# PIC24E_Extension_Schematics.net
KiCad netlist of a schematic drawn in Altium Designer
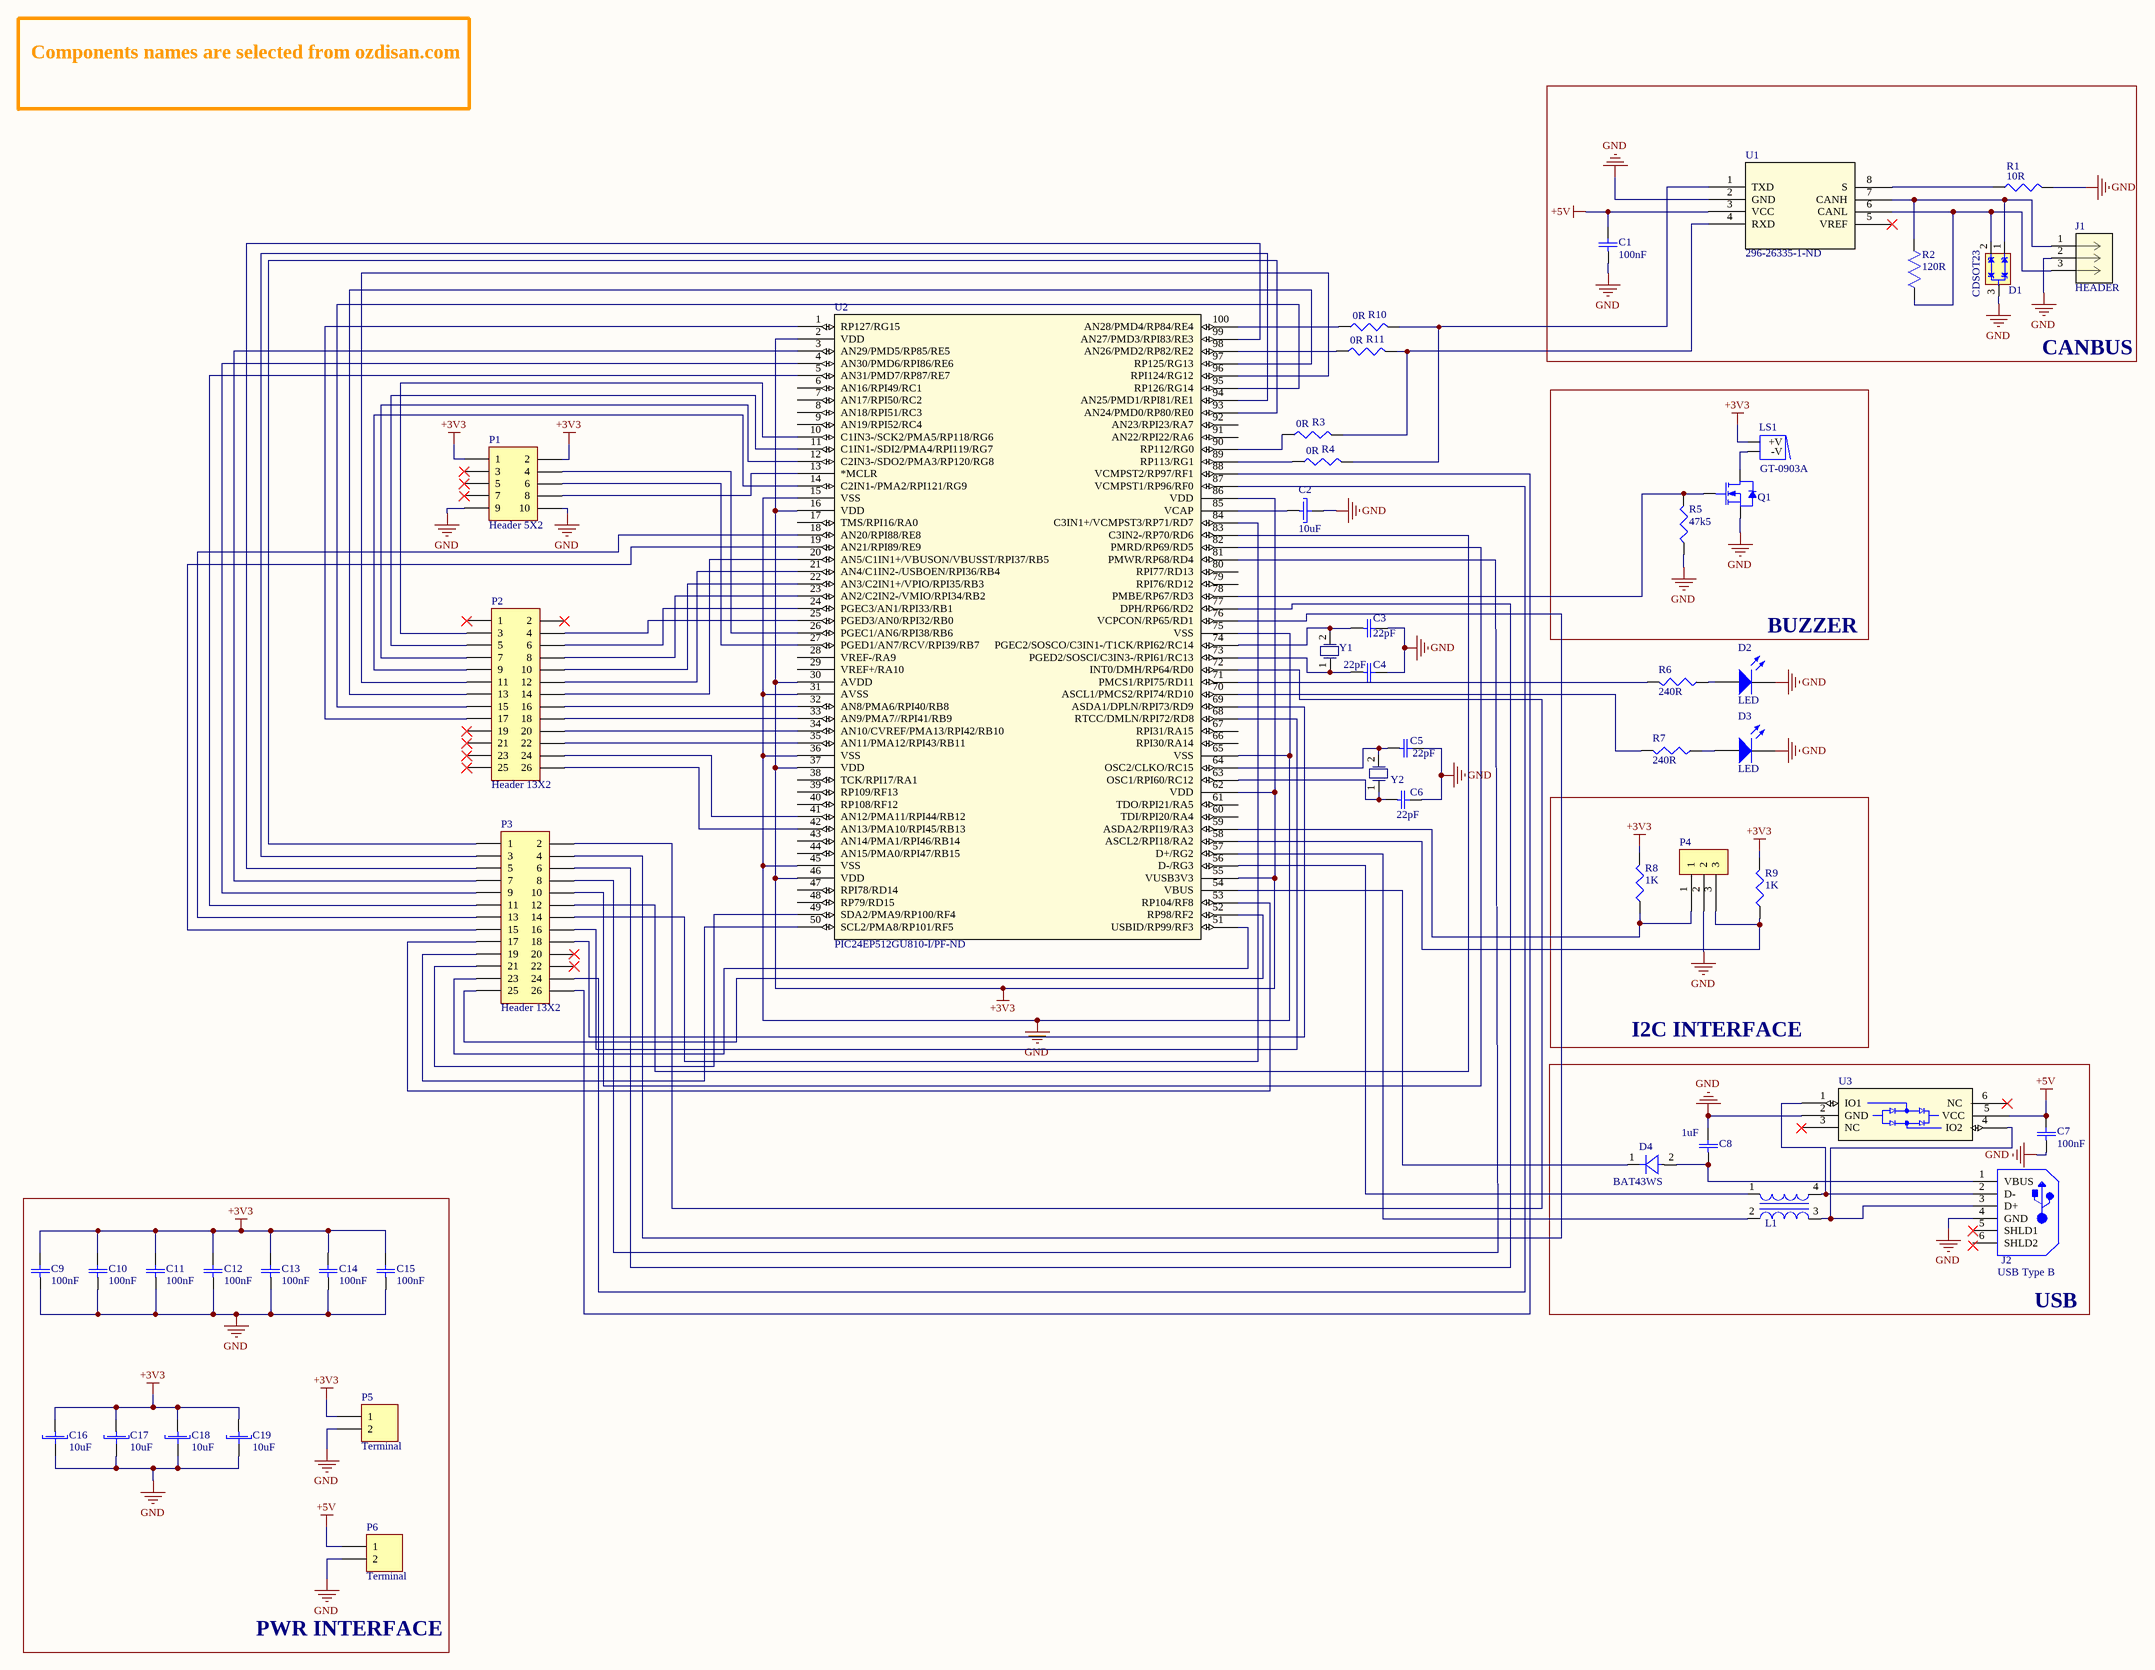
[diagram p0: PIC24E_Extension_Schematics.SchDoc]

(export (version "E")
  (design (tool "Eeschema 10.0.6"))
  (components
    (comp (ref "C1")
      (value "100nF")
      (footprint "SYNCBOX_V3I1:C1206")
      (description "MLCC (3216) 1206 100nF 100VDC ±10% X7R")
      (libsource (lib "SYNCBOX_TST") (part "CL05A104KA5NNNC"))
    )
    (comp (ref "C2")
      (value "10uF")
      (footprint "C1206 - TANT")
      (description "CAP.TANTAL 10uF 16V 10% A CASE (3216) SMD")
      (libsource (lib "SYNCBOX_TST") (part "T491A106K016AT"))
    )
    (comp (ref "C3")
      (value "22pF")
      (footprint "C1206")
      (description "MLCC (3216) 1206 22pF 50VDC ±5% C0G (NP0)")
      (libsource (lib "SYNCBOX_TST") (part "CL21A226MOCLRNC"))
    )
    (comp (ref "C4")
      (value "22pF")
      (footprint "C1206")
      (description "MLCC (3216) 1206 22pF 50VDC ±5% C0G (NP0)")
      (libsource (lib "SYNCBOX_TST") (part "CL21A226MOCLRNC"))
    )
    (comp (ref "C5")
      (value "22pF")
      (footprint "C1206")
      (description "MLCC (3216) 1206 22pF 50VDC ±5% C0G (NP0)")
      (libsource (lib "SYNCBOX_TST") (part "CL21A226MOCLRNC"))
    )
    (comp (ref "C6")
      (value "22pF")
      (footprint "C1206")
      (description "MLCC (3216) 1206 22pF 50VDC ±5% C0G (NP0)")
      (libsource (lib "SYNCBOX_TST") (part "CL21A226MOCLRNC"))
    )
    (comp (ref "C7")
      (value "100nF")
      (footprint "SYNCBOX_V3I1:C1206")
      (description "MLCC (3216) 1206 100nF 100VDC ±10% X7R")
      (libsource (lib "SYNCBOX_TST") (part "CL05A104KA5NNNC"))
    )
    (comp (ref "C8")
      (value "1uF")
      (footprint "SYNCBOX_TST:C1206")
      (description "MLCC (3216) 1206 1uF 16VDC ±5% X7R")
      (libsource (lib "SYNCBOX_V3I1") (part "CGA5L3X8R1H105K1"))
    )
    (comp (ref "C9")
      (value "100nF")
      (footprint "SYNCBOX_V3I1:C1206")
      (description "MLCC (3216) 1206 100nF 100VDC ±10% X7R")
      (libsource (lib "SYNCBOX_TST") (part "CL05A104KA5NNNC"))
    )
    (comp (ref "C10")
      (value "100nF")
      (footprint "SYNCBOX_V3I1:C1206")
      (description "MLCC (3216) 1206 100nF 100VDC ±10% X7R")
      (libsource (lib "SYNCBOX_TST") (part "CL05A104KA5NNNC"))
    )
    (comp (ref "C11")
      (value "100nF")
      (footprint "SYNCBOX_V3I1:C1206")
      (description "MLCC (3216) 1206 100nF 100VDC ±10% X7R")
      (libsource (lib "SYNCBOX_TST") (part "CL05A104KA5NNNC"))
    )
    (comp (ref "C12")
      (value "100nF")
      (footprint "SYNCBOX_V3I1:C1206")
      (description "MLCC (3216) 1206 100nF 100VDC ±10% X7R")
      (libsource (lib "SYNCBOX_TST") (part "CL05A104KA5NNNC"))
    )
    (comp (ref "C13")
      (value "100nF")
      (footprint "SYNCBOX_V3I1:C1206")
      (description "MLCC (3216) 1206 100nF 100VDC ±10% X7R")
      (libsource (lib "SYNCBOX_TST") (part "CL05A104KA5NNNC"))
    )
    (comp (ref "C14")
      (value "100nF")
      (footprint "SYNCBOX_V3I1:C1206")
      (description "MLCC (3216) 1206 100nF 100VDC ±10% X7R")
      (libsource (lib "SYNCBOX_TST") (part "CL05A104KA5NNNC"))
    )
    (comp (ref "C15")
      (value "100nF")
      (footprint "SYNCBOX_V3I1:C1206")
      (description "MLCC (3216) 1206 100nF 100VDC ±10% X7R")
      (libsource (lib "SYNCBOX_TST") (part "CL05A104KA5NNNC"))
    )
    (comp (ref "C16")
      (value "10uF")
      (footprint "C1206 - TANT")
      (description "CAP.TANTAL 10uF 16V 10% A CASE (3216) SMD")
      (libsource (lib "SYNCBOX_TST") (part "T491A106K016AT"))
    )
    (comp (ref "C17")
      (value "10uF")
      (footprint "C1206 - TANT")
      (description "CAP.TANTAL 10uF 16V 10% A CASE (3216) SMD")
      (libsource (lib "SYNCBOX_TST") (part "T491A106K016AT"))
    )
    (comp (ref "C18")
      (value "10uF")
      (footprint "C1206 - TANT")
      (description "CAP.TANTAL 10uF 16V 10% A CASE (3216) SMD")
      (libsource (lib "SYNCBOX_TST") (part "T491A106K016AT"))
    )
    (comp (ref "C19")
      (value "10uF")
      (footprint "C1206 - TANT")
      (description "CAP.TANTAL 10uF 16V 10% A CASE (3216) SMD")
      (libsource (lib "SYNCBOX_TST") (part "T491A106K016AT"))
    )
    (comp (ref "D1")
      (value "CDSOT23")
      (footprint "SOT-23-3")
      (description "DIODE TVS 24VWM 40VC SOT23")
      (libsource (lib "SYNCBOX_V3I1") (part "CDSOT23"))
    )
    (comp (ref "D2")
      (value "LED")
      (footprint "D0603_Directional")
      (description "LED RED DIFFUSED 0603 SMD")
      (fields (field (name "PUBLISHER") "Altium Limited"))
      (libsource (lib "SYNCBOX_V3I1") (part "LS Q976-NR-1"))
    )
    (comp (ref "D3")
      (value "LED")
      (footprint "D0603_Directional")
      (description "LED RED DIFFUSED 0603 SMD")
      (fields (field (name "PUBLISHER") "Altium Limited"))
      (libsource (lib "SYNCBOX_V3I1") (part "LS Q976-NR-1"))
    )
    (comp (ref "D4")
      (value "BAT43WS")
      (footprint "SOD323")
      (description "DIODE SCHOTTKY 30V 200MA SOD323")
      (libsource (lib "SYNCBOX_V3I1") (part "BAT43WS-7-F"))
    )
    (comp (ref "J1")
      (value "HEADER")
      (footprint "TerminalBlock3P508")
      (description "PIN HEADER 3PIN(1x3) 2.00mm THT V/T")
      (libsource (lib "SYNCBOX_V3I1") (part "796644-3"))
    )
    (comp (ref "J2")
      (value "USB Type B")
      (footprint "USB-B RECEPTACLE")
      (description "CONNECTOR USB B TYPE RIGHT ANGLE 90C CONNFLY")
      (libsource (lib "TE Audio, Video and High Speed Serial Connectors") (part "292304-1"))
    )
    (comp (ref "L1")
      (value "ACM2012-900-2P-T002")
      (footprint "ACM2012")
      (description "CHOKE COMM MODE 90 OHM .4A SMD")
      (fields
        (field (name "MANUFACTURER") "TDK Corporation")
        (field (name "TOLERANCE") "±1%")
        (field (name ".CHECKED PCB") "CHK")
        (field (name ".CHECKED SCH") "CHK")
      )
      (libsource (lib "SYNCBOX_V3I1") (part "ACM2012-900-2P-T002"))
    )
    (comp (ref "LS1")
      (value "GT-0903A")
      (footprint "GT-0903A")
      (description "AUDIO MAGNETIC XDCR 2-4V TH")
      (libsource (lib "SYNCBOX_V3I1") (part "GT-0903A"))
    )
    (comp (ref "P1")
      (value "Header 5X2")
      (footprint "HDR2X5")
      (description "CONNECTOR 2.54MM 10P (5X2) MALE")
      (libsource (lib "Miscellaneous Connectors") (part "Header 5X2"))
    )
    (comp (ref "P2")
      (value "Header 13X2")
      (footprint "HDR2X13")
      (description "PIN HEADER 26PIN(2x13) 2.54mm THT V/T MALE 180 C")
      (libsource (lib "Miscellaneous Connectors") (part "Header 13X2"))
    )
    (comp (ref "P3")
      (value "Header 13X2")
      (footprint "HDR2X13")
      (description "PIN HEADER 26PIN(2x13) 2.54mm THT V/T MALE 180 C")
      (libsource (lib "Miscellaneous Connectors") (part "Header 13X2"))
    )
    (comp (ref "P4")
      (value "76384-303LF")
      (footprint "HDR_1x3_2.54MM_SHDR_V2")
      (description "CONN HEADER 3POS .100\" STR GOLD")
      (fields
        (field (name "MANUFACTURER") "FCI")
        (field (name ".CREATOR") "MM")
        (field (name ".CHECKED PCB") "CHK")
        (field (name ".CHECKED SCH") "CHK")
      )
      (libsource (lib "SYNCBOX_V3I1") (part "76384-303LF"))
    )
    (comp (ref "P5")
      (value "Terminal")
      (footprint "SYNCBOX_TST:SRW_TRM")
      (description "TERM.BLK.3.50MM 2P PCB TYPE GREEN")
      (libsource (lib "Miscellaneous Connectors") (part "Header 2"))
    )
    (comp (ref "P6")
      (value "Terminal")
      (footprint "SYNCBOX_TST:SRW_TRM")
      (description "TERM.BLK.5.00MM 3P PCB TYPE 0 BOY GREEN GOLTEN")
      (libsource (lib "Miscellaneous Connectors") (part "Header 2"))
    )
    (comp (ref "Q1")
      (value "MOSFET N-CH 20V 1A SOT323")
      (footprint "SC70_SOT323")
      (fields (field (name "PUBLISHER") "Altium Limited"))
      (libsource (lib "SYNCBOX_V3I1") (part "DMG1012UW-7"))
    )
    (comp (ref "R1")
      (value "10R")
      (footprint "R1206")
      (description "RES.(3216) 1206 10 Ohms 1% 1/4W-S 400PPM")
      (libsource (lib "SYNCBOX_V3I1") (part "RC0402FR-0710RL"))
    )
    (comp (ref "R2")
      (value "120R")
      (footprint "R1206")
      (description "RES.(3216) 1206 120 Ohms 1% 1/4W-S 100PPM")
      (libsource (lib "SYNCBOX_V3I1") (part "RL1632R-R120-F"))
    )
    (comp (ref "R3")
      (value "0R")
      (footprint "R1206")
      (description "RES.(3216) 1206 0 Ohms 5% 1/4W-S 800PPM")
      (libsource (lib "SYNCBOX_V3I1") (part "RC0402FR-0710RL"))
    )
    (comp (ref "R4")
      (value "0R")
      (footprint "R1206")
      (description "RES.(3216) 1206 0 Ohms 5% 1/4W-S 800PPM")
      (libsource (lib "SYNCBOX_V3I1") (part "RC0402FR-0710RL"))
    )
    (comp (ref "R5")
      (value "47k5")
      (footprint "R1206")
      (description "RES.(3216) 1206 47.5K Ohms 1% 1/4W-S 100PPM")
      (libsource (lib "SYNCBOX_V3I1") (part "RC0402FR-0747K5L"))
    )
    (comp (ref "R6")
      (value "240R")
      (footprint "R1206")
      (description "RES.(3216) 1206 240 Ohms 1% 1/4W-S 100PPM")
      (libsource (lib "SYNCBOX_V3I1") (part "RMCF0402FT240R"))
    )
    (comp (ref "R7")
      (value "240R")
      (footprint "R1206")
      (description "RES.(3216) 1206 240 Ohms 1% 1/4W-S 100PPM")
      (libsource (lib "SYNCBOX_V3I1") (part "RMCF0402FT240R"))
    )
    (comp (ref "R8")
      (value "1K")
      (footprint "R1206")
      (description "RES.(3216) 1206 1K Ohms 1% 1/4W-S 100PPM")
      (libsource (lib "SYNCBOX_V3I1") (part "ERJ-2RKF1001X"))
    )
    (comp (ref "R9")
      (value "1K")
      (footprint "R1206")
      (description "RES.(3216) 1206 1K Ohms 1% 1/4W-S 100PPM")
      (libsource (lib "SYNCBOX_V3I1") (part "ERJ-2RKF1001X"))
    )
    (comp (ref "R10")
      (value "0R")
      (footprint "R1206")
      (description "RES.(3216) 1206 0 Ohms 5% 1/4W-S 800PPM")
      (libsource (lib "SYNCBOX_V3I1") (part "RC0402FR-0710RL"))
    )
    (comp (ref "R11")
      (value "0R")
      (footprint "R1206")
      (description "RES.(3216) 1206 0 Ohms 5% 1/4W-S 800PPM")
      (libsource (lib "SYNCBOX_V3I1") (part "RC0402FR-0710RL"))
    )
    (comp (ref "U1")
      (value "296-26335-1-ND")
      (footprint "D8")
      (description "IC EMC CAN TRANSCEIVER 8-SOIC")
      (fields
        (field (name "MANUFACTURER") "Texas Instruments")
        (field (name "MANUFACTURER_PART_NUMBER") "SN65HVD1050DR")
        (field (name ".CHECKED PCB") "CHK")
        (field (name ".CHECKED SCH") "CHK")
      )
      (libsource (lib "SYNCBOX_V3I1") (part "SN65HVD1050DR"))
    )
    (comp (ref "U2")
      (value "PIC24EP512GU810-I/PF-ND")
      (footprint "TQFP100_14x14MC")
      (description "IC MCU 16BIT 512KB FLASH 100TQFP")
      (fields
        (field (name "MANUFACTURER_PART_NUMBER") "PIC24EP512GU810-I/PT")
        (field (name "BASE PART NUMBER") "PIC24EP512GU810")
        (field (name ".CHECKED PCB") "CHK")
        (field (name ".CHECKED SCH") "CHK")
      )
      (libsource (lib "SYNCBOX_TST") (part "PIC24EP512GU810-"))
    )
    (comp (ref "U3")
      (value "TVS DIODE 5V 8.1V SOT23-6")
      (footprint "21-0058I")
      (description "MAX3207E")
      (fields
        (field (name "MANUFACTURER_PART_NUMBER") "MAX3207EAUT+T")
        (field (name ".CHECKED PCB") "CHK")
        (field (name ".CHECKED SCH") "CHK")
      )
      (libsource (lib "SYNCBOX_V3I1") (part "MAX3207EAUT+T"))
    )
    (comp (ref "Y1")
      (value "XTAL-32.7680kHz")
      (footprint "SYNCBOX_TST:C0805 - OSC")
      (description "CRYSTAL 32.7680kHz 20ppm 12.5pF SMD")
      (libsource (lib "SYNCBOX_TST") (part "Crystal-8MHz"))
    )
    (comp (ref "Y2")
      (value "XTAL-8MHz")
      (footprint "SYNCBOX_TST:HC49/US")
      (description "CRYSTAL 8.0000MHZ 18PF SMD")
      (libsource (lib "SYNCBOX_TST") (part "Crystal-8MHz"))
    )
  )
  (nets
    (net (code "1") (name "+3V3") (class "Default")
      (node (ref "C10") (pin "2") (pinfunction "2_2") (pintype "passive"))
      (node (ref "C11") (pin "2") (pinfunction "2_2") (pintype "passive"))
      (node (ref "C12") (pin "2") (pinfunction "2_2") (pintype "passive"))
      (node (ref "C13") (pin "2") (pinfunction "2_2") (pintype "passive"))
      (node (ref "C14") (pin "2") (pinfunction "2_2") (pintype "passive"))
      (node (ref "C15") (pin "2") (pinfunction "2_2") (pintype "passive"))
      (node (ref "C16") (pin "1") (pinfunction "1_1") (pintype "passive"))
      (node (ref "C17") (pin "1") (pinfunction "1_1") (pintype "passive"))
      (node (ref "C18") (pin "1") (pinfunction "1_1") (pintype "passive"))
      (node (ref "C19") (pin "1") (pinfunction "1_1") (pintype "passive"))
      (node (ref "C9") (pin "2") (pinfunction "2_2") (pintype "passive"))
      (node (ref "LS1") (pin "1") (pinfunction "+V_1") (pintype "passive"))
      (node (ref "P1") (pin "1") (pinfunction "1_1") (pintype "passive"))
      (node (ref "P1") (pin "2") (pinfunction "2_2") (pintype "passive"))
      (node (ref "P5") (pin "1") (pinfunction "1_1") (pintype "passive"))
      (node (ref "R8") (pin "2") (pinfunction "2_2") (pintype "passive"))
      (node (ref "R9") (pin "2") (pinfunction "2_2") (pintype "passive"))
      (node (ref "U2") (pin "16") (pinfunction "VDD_16") (pintype "passive"))
      (node (ref "U2") (pin "2") (pinfunction "VDD_2") (pintype "passive"))
      (node (ref "U2") (pin "30") (pinfunction "AVDD_30") (pintype "passive"))
      (node (ref "U2") (pin "37") (pinfunction "VDD_37") (pintype "passive"))
      (node (ref "U2") (pin "46") (pinfunction "VDD_46") (pintype "passive"))
      (node (ref "U2") (pin "55") (pinfunction "VUSB3V3_55") (pintype "passive"))
      (node (ref "U2") (pin "62") (pinfunction "VDD_62") (pintype "passive"))
      (node (ref "U2") (pin "86") (pinfunction "VDD_86") (pintype "passive"))
    )
    (net (code "2") (name "+5V") (class "Default")
      (node (ref "C1") (pin "2") (pinfunction "2_2") (pintype "passive"))
      (node (ref "C7") (pin "2") (pinfunction "2_2") (pintype "passive"))
      (node (ref "P6") (pin "1") (pinfunction "1_1") (pintype "passive"))
      (node (ref "U1") (pin "3") (pinfunction "VCC_3") (pintype "power_in"))
      (node (ref "U3") (pin "5") (pinfunction "VCC_5") (pintype "power_in"))
    )
    (net (code "3") (name "GND") (class "Default")
      (node (ref "C1") (pin "1") (pinfunction "1_1") (pintype "passive"))
      (node (ref "C10") (pin "1") (pinfunction "1_1") (pintype "passive"))
      (node (ref "C11") (pin "1") (pinfunction "1_1") (pintype "passive"))
      (node (ref "C12") (pin "1") (pinfunction "1_1") (pintype "passive"))
      (node (ref "C13") (pin "1") (pinfunction "1_1") (pintype "passive"))
      (node (ref "C14") (pin "1") (pinfunction "1_1") (pintype "passive"))
      (node (ref "C15") (pin "1") (pinfunction "1_1") (pintype "passive"))
      (node (ref "C16") (pin "2") (pinfunction "2_2") (pintype "passive"))
      (node (ref "C17") (pin "2") (pinfunction "2_2") (pintype "passive"))
      (node (ref "C18") (pin "2") (pinfunction "2_2") (pintype "passive"))
      (node (ref "C19") (pin "2") (pinfunction "2_2") (pintype "passive"))
      (node (ref "C2") (pin "2") (pinfunction "2_2") (pintype "passive"))
      (node (ref "C3") (pin "2") (pinfunction "2_2") (pintype "passive"))
      (node (ref "C4") (pin "2") (pinfunction "2_2") (pintype "passive"))
      (node (ref "C5") (pin "2") (pinfunction "2_2") (pintype "passive"))
      (node (ref "C6") (pin "2") (pinfunction "2_2") (pintype "passive"))
      (node (ref "C7") (pin "1") (pinfunction "1_1") (pintype "passive"))
      (node (ref "C8") (pin "2") (pinfunction "2_2") (pintype "passive"))
      (node (ref "C9") (pin "1") (pinfunction "1_1") (pintype "passive"))
      (node (ref "D1") (pin "3") (pinfunction "3_3") (pintype "passive"))
      (node (ref "D2") (pin "2") (pinfunction "K_2") (pintype "passive"))
      (node (ref "D3") (pin "2") (pinfunction "K_2") (pintype "passive"))
      (node (ref "J1") (pin "2") (pinfunction "2_2") (pintype "passive"))
      (node (ref "J2") (pin "4") (pinfunction "GND_4") (pintype "passive"))
      (node (ref "P1") (pin "10") (pinfunction "10_10") (pintype "passive"))
      (node (ref "P1") (pin "9") (pinfunction "9_9") (pintype "passive"))
      (node (ref "P4") (pin "2") (pinfunction "2_2") (pintype "passive"))
      (node (ref "P5") (pin "2") (pinfunction "2_2") (pintype "passive"))
      (node (ref "P6") (pin "2") (pinfunction "2_2") (pintype "passive"))
      (node (ref "Q1") (pin "2") (pinfunction "S_2") (pintype "passive"))
      (node (ref "R1") (pin "2") (pinfunction "2_2") (pintype "passive"))
      (node (ref "R5") (pin "1") (pinfunction "1_1") (pintype "passive"))
      (node (ref "U1") (pin "2") (pinfunction "GND_2") (pintype "power_in"))
      (node (ref "U2") (pin "15") (pinfunction "VSS_15") (pintype "passive"))
      (node (ref "U2") (pin "31") (pinfunction "AVSS_31") (pintype "passive"))
      (node (ref "U2") (pin "36") (pinfunction "VSS_36") (pintype "passive"))
      (node (ref "U2") (pin "45") (pinfunction "VSS_45") (pintype "passive"))
      (node (ref "U2") (pin "65") (pinfunction "VSS_65") (pintype "passive"))
      (node (ref "U2") (pin "75") (pinfunction "VSS_75") (pintype "passive"))
      (node (ref "U3") (pin "2") (pinfunction "GND_2") (pintype "power_in"))
    )
    (net (code "4") (name "Net-(D2-A)") (class "Default")
      (node (ref "D2") (pin "1") (pinfunction "A_1") (pintype "passive"))
      (node (ref "R6") (pin "1") (pinfunction "1_1") (pintype "passive"))
    )
    (net (code "5") (name "Net-(D3-A)") (class "Default")
      (node (ref "D3") (pin "1") (pinfunction "A_1") (pintype "passive"))
      (node (ref "R7") (pin "1") (pinfunction "1_1") (pintype "passive"))
    )
    (net (code "6") (name "Net-(J2-D+)") (class "Default")
      (node (ref "J2") (pin "3") (pinfunction "D+_3") (pintype "passive"))
      (node (ref "L1") (pin "3") (pinfunction "3_3") (pintype "passive"))
      (node (ref "U3") (pin "4") (pinfunction "IO2_4") (pintype "bidirectional"))
    )
    (net (code "7") (name "Net-(J2-D-)") (class "Default")
      (node (ref "J2") (pin "2") (pinfunction "D-_2") (pintype "passive"))
      (node (ref "L1") (pin "4") (pinfunction "4_4") (pintype "passive"))
      (node (ref "U3") (pin "1") (pinfunction "IO1_1") (pintype "bidirectional"))
    )
    (net (code "8") (name "Net-(J2-VBUS)") (class "Default")
      (node (ref "C8") (pin "1") (pinfunction "1_1") (pintype "passive"))
      (node (ref "D4") (pin "2") (pinfunction "2_2") (pintype "passive"))
      (node (ref "J2") (pin "1") (pinfunction "VBUS_1") (pintype "passive"))
    )
    (net (code "9") (name "Net-(LS1--V)") (class "Default")
      (node (ref "LS1") (pin "2") (pinfunction "-V_2") (pintype "passive"))
      (node (ref "Q1") (pin "3") (pinfunction "D_3") (pintype "passive"))
    )
    (net (code "10") (name "Net-(Q1-G)") (class "Default")
      (node (ref "Q1") (pin "1") (pinfunction "G_1") (pintype "passive"))
      (node (ref "R5") (pin "2") (pinfunction "2_2") (pintype "passive"))
      (node (ref "U2") (pin "78") (pinfunction "PMBE/RP67/RD3_78") (pintype "bidirectional"))
    )
    (net (code "11") (name "Net-(U1-CANH)") (class "Default")
      (node (ref "D1") (pin "1") (pinfunction "1_1") (pintype "passive"))
      (node (ref "J1") (pin "1") (pinfunction "1_1") (pintype "passive"))
      (node (ref "R2") (pin "2") (pinfunction "2_2") (pintype "passive"))
      (node (ref "U1") (pin "7") (pinfunction "CANH_7") (pintype "passive"))
    )
    (net (code "12") (name "Net-(U1-CANL)") (class "Default")
      (node (ref "D1") (pin "2") (pinfunction "2_2") (pintype "passive"))
      (node (ref "J1") (pin "3") (pinfunction "3_3") (pintype "passive"))
      (node (ref "R2") (pin "1") (pinfunction "1_1") (pintype "passive"))
      (node (ref "U1") (pin "6") (pinfunction "CANL_6") (pintype "passive"))
    )
    (net (code "13") (name "Net-(U1-RXD)") (class "Default")
      (node (ref "R11") (pin "2") (pinfunction "2_2") (pintype "passive"))
      (node (ref "R3") (pin "2") (pinfunction "2_2") (pintype "passive"))
      (node (ref "U1") (pin "4") (pinfunction "RXD_4") (pintype "passive"))
    )
    (net (code "14") (name "Net-(U1-S)") (class "Default")
      (node (ref "R1") (pin "1") (pinfunction "1_1") (pintype "passive"))
      (node (ref "U1") (pin "8") (pinfunction "S_8") (pintype "passive"))
    )
    (net (code "15") (name "Net-(U1-TXD)") (class "Default")
      (node (ref "R10") (pin "2") (pinfunction "2_2") (pintype "passive"))
      (node (ref "R4") (pin "2") (pinfunction "2_2") (pintype "passive"))
      (node (ref "U1") (pin "1") (pinfunction "TXD_1") (pintype "passive"))
    )
    (net (code "16") (name "Net-(U2-*MCLR)") (class "Default")
      (node (ref "P1") (pin "8") (pinfunction "8_8") (pintype "passive"))
      (node (ref "U2") (pin "13") (pinfunction "*MCLR_13") (pintype "passive"))
    )
    (net (code "17") (name "Net-(U2-AN2{slash}C2IN2-{slash}VMIO{slash}RPI34{slash}RB2)") (class "Default")
      (node (ref "P2") (pin "8") (pinfunction "8_8") (pintype "passive"))
      (node (ref "U2") (pin "23") (pinfunction "AN2/C2IN2-/VMIO/RPI34/RB2_23") (pintype "bidirectional"))
    )
    (net (code "18") (name "Net-(U2-AN3{slash}C2IN1+{slash}VPIO{slash}RPI35{slash}RB3)") (class "Default")
      (node (ref "P2") (pin "10") (pinfunction "10_10") (pintype "passive"))
      (node (ref "U2") (pin "22") (pinfunction "AN3/C2IN1+/VPIO/RPI35/RB3_22") (pintype "bidirectional"))
    )
    (net (code "19") (name "Net-(U2-AN4{slash}C1IN2-{slash}USBOEN{slash}RPI36{slash}RB4)") (class "Default")
      (node (ref "P2") (pin "12") (pinfunction "12_12") (pintype "passive"))
      (node (ref "U2") (pin "21") (pinfunction "AN4/C1IN2-/USBOEN/RPI36/RB4_21") (pintype "bidirectional"))
    )
    (net (code "20") (name "Net-(U2-AN5{slash}C1IN1+{slash}VBUSON{slash}VBUSST{slash}RPI37{slash}RB5)") (class "Default")
      (node (ref "P2") (pin "14") (pinfunction "14_14") (pintype "passive"))
      (node (ref "U2") (pin "20") (pinfunction "AN5/C1IN1+/VBUSON/VBUSST/RPI37/RB5_20") (pintype "bidirectional"))
    )
    (net (code "21") (name "Net-(U2-AN8{slash}PMA6{slash}RPI40{slash}RB8)") (class "Default")
      (node (ref "P2") (pin "16") (pinfunction "16_16") (pintype "passive"))
      (node (ref "U2") (pin "32") (pinfunction "AN8/PMA6/RPI40/RB8_32") (pintype "bidirectional"))
    )
    (net (code "22") (name "Net-(U2-AN9{slash}PMA7{slash}{slash}RPI41{slash}RB9)") (class "Default")
      (node (ref "P2") (pin "18") (pinfunction "18_18") (pintype "passive"))
      (node (ref "U2") (pin "33") (pinfunction "AN9/PMA7//RPI41/RB9_33") (pintype "bidirectional"))
    )
    (net (code "23") (name "Net-(U2-AN10{slash}CVREF{slash}PMA13{slash}RPI42{slash}RB10)") (class "Default")
      (node (ref "P2") (pin "20") (pinfunction "20_20") (pintype "passive"))
      (node (ref "U2") (pin "34") (pinfunction "AN10/CVREF/PMA13/RPI42/RB10_34") (pintype "bidirectional"))
    )
    (net (code "24") (name "Net-(U2-AN11{slash}PMA12{slash}RPI43{slash}RB11)") (class "Default")
      (node (ref "P2") (pin "22") (pinfunction "22_22") (pintype "passive"))
      (node (ref "U2") (pin "35") (pinfunction "AN11/PMA12/RPI43/RB11_35") (pintype "bidirectional"))
    )
    (net (code "25") (name "Net-(U2-AN12{slash}PMA11{slash}RPI44{slash}RB12)") (class "Default")
      (node (ref "P2") (pin "24") (pinfunction "24_24") (pintype "passive"))
      (node (ref "U2") (pin "41") (pinfunction "AN12/PMA11/RPI44/RB12_41") (pintype "bidirectional"))
    )
    (net (code "26") (name "Net-(U2-AN13{slash}PMA10{slash}RPI45{slash}RB13)") (class "Default")
      (node (ref "P2") (pin "26") (pinfunction "26_26") (pintype "passive"))
      (node (ref "U2") (pin "42") (pinfunction "AN13/PMA10/RPI45/RB13_42") (pintype "bidirectional"))
    )
    (net (code "27") (name "Net-(U2-AN20{slash}RPI88{slash}RE8)") (class "Default")
      (node (ref "P3") (pin "13") (pinfunction "13_13") (pintype "passive"))
      (node (ref "U2") (pin "18") (pinfunction "AN20/RPI88/RE8_18") (pintype "bidirectional"))
    )
    (net (code "28") (name "Net-(U2-AN21{slash}RPI89{slash}RE9)") (class "Default")
      (node (ref "P3") (pin "15") (pinfunction "15_15") (pintype "passive"))
      (node (ref "U2") (pin "19") (pinfunction "AN21/RPI89/RE9_19") (pintype "bidirectional"))
    )
    (net (code "29") (name "Net-(U2-AN24{slash}PMD0{slash}RP80{slash}RE0)") (class "Default")
      (node (ref "P3") (pin "1") (pinfunction "1_1") (pintype "passive"))
      (node (ref "U2") (pin "93") (pinfunction "AN24/PMD0/RP80/RE0_93") (pintype "bidirectional"))
    )
    (net (code "30") (name "Net-(U2-AN25{slash}PMD1{slash}RPI81{slash}RE1)") (class "Default")
      (node (ref "P3") (pin "3") (pinfunction "3_3") (pintype "passive"))
      (node (ref "U2") (pin "94") (pinfunction "AN25/PMD1/RPI81/RE1_94") (pintype "bidirectional"))
    )
    (net (code "31") (name "Net-(U2-AN26{slash}PMD2{slash}RP82{slash}RE2)") (class "Default")
      (node (ref "R11") (pin "1") (pinfunction "1_1") (pintype "passive"))
      (node (ref "U2") (pin "98") (pinfunction "AN26/PMD2/RP82/RE2_98") (pintype "bidirectional"))
    )
    (net (code "32") (name "Net-(U2-AN27{slash}PMD3{slash}RPI83{slash}RE3)") (class "Default")
      (node (ref "P3") (pin "5") (pinfunction "5_5") (pintype "passive"))
      (node (ref "U2") (pin "99") (pinfunction "AN27/PMD3/RPI83/RE3_99") (pintype "bidirectional"))
    )
    (net (code "33") (name "Net-(U2-AN28{slash}PMD4{slash}RP84{slash}RE4)") (class "Default")
      (node (ref "R10") (pin "1") (pinfunction "1_1") (pintype "passive"))
      (node (ref "U2") (pin "100") (pinfunction "AN28/PMD4/RP84/RE4_100") (pintype "bidirectional"))
    )
    (net (code "34") (name "Net-(U2-AN29{slash}PMD5{slash}RP85{slash}RE5)") (class "Default")
      (node (ref "P3") (pin "7") (pinfunction "7_7") (pintype "passive"))
      (node (ref "U2") (pin "3") (pinfunction "AN29/PMD5/RP85/RE5_3") (pintype "bidirectional"))
    )
    (net (code "35") (name "Net-(U2-AN30{slash}PMD6{slash}RPI86{slash}RE6)") (class "Default")
      (node (ref "P3") (pin "9") (pinfunction "9_9") (pintype "passive"))
      (node (ref "U2") (pin "4") (pinfunction "AN30/PMD6/RPI86/RE6_4") (pintype "bidirectional"))
    )
    (net (code "36") (name "Net-(U2-AN31{slash}PMD7{slash}RP87{slash}RE7)") (class "Default")
      (node (ref "P3") (pin "11") (pinfunction "11_11") (pintype "passive"))
      (node (ref "U2") (pin "5") (pinfunction "AN31/PMD7/RP87/RE7_5") (pintype "bidirectional"))
    )
    (net (code "37") (name "Net-(U2-ASCL1{slash}PMCS2{slash}RPI74{slash}RD10)") (class "Default")
      (node (ref "R7") (pin "2") (pinfunction "2_2") (pintype "passive"))
      (node (ref "U2") (pin "70") (pinfunction "ASCL1/PMCS2/RPI74/RD10_70") (pintype "bidirectional"))
    )
    (net (code "38") (name "Net-(U2-ASCL2{slash}RPI18{slash}RA2)") (class "Default")
      (node (ref "P4") (pin "3") (pinfunction "3_3") (pintype "passive"))
      (node (ref "R9") (pin "1") (pinfunction "1_1") (pintype "passive"))
      (node (ref "U2") (pin "58") (pinfunction "ASCL2/RPI18/RA2_58") (pintype "bidirectional"))
    )
    (net (code "39") (name "Net-(U2-ASDA1{slash}DPLN{slash}RPI73{slash}RD9)") (class "Default")
      (node (ref "P3") (pin "18") (pinfunction "18_18") (pintype "passive"))
      (node (ref "U2") (pin "69") (pinfunction "ASDA1/DPLN/RPI73/RD9_69") (pintype "bidirectional"))
    )
    (net (code "40") (name "Net-(U2-ASDA2{slash}RPI19{slash}RA3)") (class "Default")
      (node (ref "P4") (pin "1") (pinfunction "1_1") (pintype "passive"))
      (node (ref "R8") (pin "1") (pinfunction "1_1") (pintype "passive"))
      (node (ref "U2") (pin "59") (pinfunction "ASDA2/RPI19/RA3_59") (pintype "bidirectional"))
    )
    (net (code "41") (name "Net-(U2-C1IN1-{slash}SDI2{slash}PMA4{slash}RPI119{slash}RG7)") (class "Default")
      (node (ref "P2") (pin "5") (pinfunction "5_5") (pintype "passive"))
      (node (ref "U2") (pin "11") (pinfunction "C1IN1-/SDI2/PMA4/RPI119/RG7_11") (pintype "bidirectional"))
    )
    (net (code "42") (name "Net-(U2-C1IN3-{slash}SCK2{slash}PMA5{slash}RP118{slash}RG6)") (class "Default")
      (node (ref "P2") (pin "3") (pinfunction "3_3") (pintype "passive"))
      (node (ref "U2") (pin "10") (pinfunction "C1IN3-/SCK2/PMA5/RP118/RG6_10") (pintype "bidirectional"))
    )
    (net (code "43") (name "Net-(U2-C2IN1-{slash}PMA2{slash}RPI121{slash}RG9)") (class "Default")
      (node (ref "P2") (pin "9") (pinfunction "9_9") (pintype "passive"))
      (node (ref "U2") (pin "14") (pinfunction "C2IN1-/PMA2/RPI121/RG9_14") (pintype "bidirectional"))
    )
    (net (code "44") (name "Net-(U2-C2IN3-{slash}SDO2{slash}PMA3{slash}RP120{slash}RG8)") (class "Default")
      (node (ref "P2") (pin "7") (pinfunction "7_7") (pintype "passive"))
      (node (ref "U2") (pin "12") (pinfunction "C2IN3-/SDO2/PMA3/RP120/RG8_12") (pintype "bidirectional"))
    )
    (net (code "45") (name "Net-(U2-C3IN1+{slash}VCMPST3{slash}RP71{slash}RD7)") (class "Default")
      (node (ref "P3") (pin "14") (pinfunction "14_14") (pintype "passive"))
      (node (ref "U2") (pin "84") (pinfunction "C3IN1+/VCMPST3/RP71/RD7_84") (pintype "bidirectional"))
    )
    (net (code "46") (name "Net-(U2-C3IN2-{slash}RP70{slash}RD6)") (class "Default")
      (node (ref "P3") (pin "12") (pinfunction "12_12") (pintype "passive"))
      (node (ref "U2") (pin "83") (pinfunction "C3IN2-/RP70/RD6_83") (pintype "bidirectional"))
    )
    (net (code "47") (name "Net-(U2-D+{slash}RG2)") (class "Default")
      (node (ref "L1") (pin "2") (pinfunction "2_2") (pintype "passive"))
      (node (ref "U2") (pin "57") (pinfunction "D+/RG2_57") (pintype "bidirectional"))
    )
    (net (code "48") (name "Net-(U2-D-{slash}RG3)") (class "Default")
      (node (ref "L1") (pin "1") (pinfunction "1_1") (pintype "passive"))
      (node (ref "U2") (pin "56") (pinfunction "D-/RG3_56") (pintype "bidirectional"))
    )
    (net (code "49") (name "Net-(U2-DPH{slash}RP66{slash}RD2)") (class "Default")
      (node (ref "P3") (pin "6") (pinfunction "6_6") (pintype "passive"))
      (node (ref "U2") (pin "77") (pinfunction "DPH/RP66/RD2_77") (pintype "bidirectional"))
    )
    (net (code "50") (name "Net-(U2-INT0{slash}DMH{slash}RP64{slash}RD0)") (class "Default")
      (node (ref "P3") (pin "2") (pinfunction "2_2") (pintype "passive"))
      (node (ref "U2") (pin "72") (pinfunction "INT0/DMH/RP64/RD0_72") (pintype "bidirectional"))
    )
    (net (code "51") (name "Net-(U2-OSC1{slash}RPI60{slash}RC12)") (class "Default")
      (node (ref "C6") (pin "1") (pinfunction "1_1") (pintype "passive"))
      (node (ref "U2") (pin "63") (pinfunction "OSC1/RPI60/RC12_63") (pintype "bidirectional"))
      (node (ref "Y2") (pin "1") (pinfunction "1_1") (pintype "passive"))
    )
    (net (code "52") (name "Net-(U2-OSC2{slash}CLKO{slash}RC15)") (class "Default")
      (node (ref "C5") (pin "1") (pinfunction "1_1") (pintype "passive"))
      (node (ref "U2") (pin "64") (pinfunction "OSC2/CLKO/RC15_64") (pintype "bidirectional"))
      (node (ref "Y2") (pin "2") (pinfunction "2_2") (pintype "passive"))
    )
    (net (code "53") (name "Net-(U2-PGEC1{slash}AN6{slash}RPI38{slash}RB6)") (class "Default")
      (node (ref "P1") (pin "4") (pinfunction "4_4") (pintype "passive"))
      (node (ref "U2") (pin "26") (pinfunction "PGEC1/AN6/RPI38/RB6_26") (pintype "bidirectional"))
    )
    (net (code "54") (name "Net-(U2-PGEC2{slash}SOSCO{slash}C3IN1-{slash}T1CK{slash}RPI62{slash}RC14)") (class "Default")
      (node (ref "C3") (pin "1") (pinfunction "1_1") (pintype "passive"))
      (node (ref "U2") (pin "74") (pinfunction "PGEC2/SOSCO/C3IN1-/T1CK/RPI62/RC14_74") (pintype "bidirectional"))
      (node (ref "Y1") (pin "2") (pinfunction "2_2") (pintype "passive"))
    )
    (net (code "55") (name "Net-(U2-PGEC3{slash}AN1{slash}RPI33{slash}RB1)") (class "Default")
      (node (ref "P2") (pin "6") (pinfunction "6_6") (pintype "passive"))
      (node (ref "U2") (pin "24") (pinfunction "PGEC3/AN1/RPI33/RB1_24") (pintype "bidirectional"))
    )
    (net (code "56") (name "Net-(U2-PGED1{slash}AN7{slash}RCV{slash}RPI39{slash}RB7)") (class "Default")
      (node (ref "P1") (pin "6") (pinfunction "6_6") (pintype "passive"))
      (node (ref "U2") (pin "27") (pinfunction "PGED1/AN7/RCV/RPI39/RB7_27") (pintype "bidirectional"))
    )
    (net (code "57") (name "Net-(U2-PGED2{slash}SOSCI{slash}C3IN3-{slash}RPI61{slash}RC13)") (class "Default")
      (node (ref "C4") (pin "1") (pinfunction "1_1") (pintype "passive"))
      (node (ref "U2") (pin "73") (pinfunction "PGED2/SOSCI/C3IN3-/RPI61/RC13_73") (pintype "bidirectional"))
      (node (ref "Y1") (pin "1") (pinfunction "1_1") (pintype "passive"))
    )
    (net (code "58") (name "Net-(U2-PGED3{slash}AN0{slash}RPI32{slash}RB0)") (class "Default")
      (node (ref "P2") (pin "4") (pinfunction "4_4") (pintype "passive"))
      (node (ref "U2") (pin "25") (pinfunction "PGED3/AN0/RPI32/RB0_25") (pintype "bidirectional"))
    )
    (net (code "59") (name "Net-(U2-PMCS1{slash}RPI75{slash}RD11)") (class "Default")
      (node (ref "R6") (pin "2") (pinfunction "2_2") (pintype "passive"))
      (node (ref "U2") (pin "71") (pinfunction "PMCS1/RPI75/RD11_71") (pintype "bidirectional"))
    )
    (net (code "60") (name "Net-(U2-PMRD{slash}RP69{slash}RD5)") (class "Default")
      (node (ref "P3") (pin "10") (pinfunction "10_10") (pintype "passive"))
      (node (ref "U2") (pin "82") (pinfunction "PMRD/RP69/RD5_82") (pintype "bidirectional"))
    )
    (net (code "61") (name "Net-(U2-PMWR{slash}RP68{slash}RD4)") (class "Default")
      (node (ref "P3") (pin "8") (pinfunction "8_8") (pintype "passive"))
      (node (ref "U2") (pin "81") (pinfunction "PMWR/RP68/RD4_81") (pintype "bidirectional"))
    )
    (net (code "62") (name "Net-(U2-RP98{slash}RF2)") (class "Default")
      (node (ref "P3") (pin "25") (pinfunction "25_25") (pintype "passive"))
      (node (ref "U2") (pin "52") (pinfunction "RP98/RF2_52") (pintype "bidirectional"))
    )
    (net (code "63") (name "Net-(U2-RP104{slash}RF8)") (class "Default")
      (node (ref "P3") (pin "17") (pinfunction "17_17") (pintype "passive"))
      (node (ref "U2") (pin "53") (pinfunction "RP104/RF8_53") (pintype "bidirectional"))
    )
    (net (code "64") (name "Net-(U2-RP112{slash}RG0)") (class "Default")
      (node (ref "R3") (pin "1") (pinfunction "1_1") (pintype "passive"))
      (node (ref "U2") (pin "90") (pinfunction "RP112/RG0_90") (pintype "bidirectional"))
    )
    (net (code "65") (name "Net-(U2-RP113{slash}RG1)") (class "Default")
      (node (ref "R4") (pin "1") (pinfunction "1_1") (pintype "passive"))
      (node (ref "U2") (pin "89") (pinfunction "RP113/RG1_89") (pintype "bidirectional"))
    )
    (net (code "66") (name "Net-(U2-RP125{slash}RG13)") (class "Default")
      (node (ref "P2") (pin "13") (pinfunction "13_13") (pintype "passive"))
      (node (ref "U2") (pin "97") (pinfunction "RP125/RG13_97") (pintype "bidirectional"))
    )
    (net (code "67") (name "Net-(U2-RP126{slash}RG14)") (class "Default")
      (node (ref "P2") (pin "15") (pinfunction "15_15") (pintype "passive"))
      (node (ref "U2") (pin "95") (pinfunction "RP126/RG14_95") (pintype "bidirectional"))
    )
    (net (code "68") (name "Net-(U2-RP127{slash}RG15)") (class "Default")
      (node (ref "P2") (pin "17") (pinfunction "17_17") (pintype "passive"))
      (node (ref "U2") (pin "1") (pinfunction "RP127/RG15_1") (pintype "bidirectional"))
    )
    (net (code "69") (name "Net-(U2-RPI124{slash}RG12)") (class "Default")
      (node (ref "P2") (pin "11") (pinfunction "11_11") (pintype "passive"))
      (node (ref "U2") (pin "96") (pinfunction "RPI124/RG12_96") (pintype "bidirectional"))
    )
    (net (code "70") (name "Net-(U2-RTCC{slash}DMLN{slash}RPI72{slash}RD8)") (class "Default")
      (node (ref "P3") (pin "16") (pinfunction "16_16") (pintype "passive"))
      (node (ref "U2") (pin "68") (pinfunction "RTCC/DMLN/RPI72/RD8_68") (pintype "bidirectional"))
    )
    (net (code "71") (name "Net-(U2-SCL2{slash}PMA8{slash}RP101{slash}RF5)") (class "Default")
      (node (ref "P3") (pin "19") (pinfunction "19_19") (pintype "passive"))
      (node (ref "U2") (pin "50") (pinfunction "SCL2/PMA8/RP101/RF5_50") (pintype "bidirectional"))
    )
    (net (code "72") (name "Net-(U2-SDA2{slash}PMA9{slash}RP100{slash}RF4)") (class "Default")
      (node (ref "P3") (pin "21") (pinfunction "21_21") (pintype "passive"))
      (node (ref "U2") (pin "49") (pinfunction "SDA2/PMA9/RP100/RF4_49") (pintype "bidirectional"))
    )
    (net (code "73") (name "Net-(U2-USBID{slash}RP99{slash}RF3)") (class "Default")
      (node (ref "P3") (pin "23") (pinfunction "23_23") (pintype "passive"))
      (node (ref "U2") (pin "51") (pinfunction "USBID/RP99/RF3_51") (pintype "bidirectional"))
    )
    (net (code "74") (name "Net-(U2-VBUS)") (class "Default")
      (node (ref "D4") (pin "1") (pinfunction "1_1") (pintype "passive"))
      (node (ref "U2") (pin "54") (pinfunction "VBUS_54") (pintype "passive"))
    )
    (net (code "75") (name "Net-(U2-VCAP)") (class "Default")
      (node (ref "C2") (pin "1") (pinfunction "1_1") (pintype "passive"))
      (node (ref "U2") (pin "85") (pinfunction "VCAP_85") (pintype "passive"))
    )
    (net (code "76") (name "Net-(U2-VCMPST1{slash}RP96{slash}RF0)") (class "Default")
      (node (ref "P3") (pin "24") (pinfunction "24_24") (pintype "passive"))
      (node (ref "U2") (pin "87") (pinfunction "VCMPST1/RP96/RF0_87") (pintype "bidirectional"))
    )
    (net (code "77") (name "Net-(U2-VCMPST2{slash}RP97{slash}RF1)") (class "Default")
      (node (ref "P3") (pin "26") (pinfunction "26_26") (pintype "passive"))
      (node (ref "U2") (pin "88") (pinfunction "VCMPST2/RP97/RF1_88") (pintype "bidirectional"))
    )
    (net (code "78") (name "Net-(U2-VCPCON{slash}RP65{slash}RD1)") (class "Default")
      (node (ref "P3") (pin "4") (pinfunction "4_4") (pintype "passive"))
      (node (ref "U2") (pin "76") (pinfunction "VCPCON/RP65/RD1_76") (pintype "bidirectional"))
    )
    (net (code "79") (name "unconnected-(J2-SHLD1-Pad5)") (class "Default")
      (node (ref "J2") (pin "5") (pinfunction "SHLD1_5") (pintype "passive+no_connect"))
    )
    (net (code "80") (name "unconnected-(J2-SHLD2-Pad6)") (class "Default")
      (node (ref "J2") (pin "6") (pinfunction "SHLD2_6") (pintype "passive"))
    )
    (net (code "81") (name "unconnected-(P1-Pad3)") (class "Default")
      (node (ref "P1") (pin "3") (pinfunction "3_3") (pintype "passive+no_connect"))
    )
    (net (code "82") (name "unconnected-(P1-Pad5)") (class "Default")
      (node (ref "P1") (pin "5") (pinfunction "5_5") (pintype "passive+no_connect"))
    )
    (net (code "83") (name "unconnected-(P1-Pad7)") (class "Default")
      (node (ref "P1") (pin "7") (pinfunction "7_7") (pintype "passive+no_connect"))
    )
    (net (code "84") (name "unconnected-(P2-Pad1)") (class "Default")
      (node (ref "P2") (pin "1") (pinfunction "1_1") (pintype "passive+no_connect"))
    )
    (net (code "85") (name "unconnected-(P2-Pad2)") (class "Default")
      (node (ref "P2") (pin "2") (pinfunction "2_2") (pintype "passive+no_connect"))
    )
    (net (code "86") (name "unconnected-(P2-Pad19)") (class "Default")
      (node (ref "P2") (pin "19") (pinfunction "19_19") (pintype "passive+no_connect"))
    )
    (net (code "87") (name "unconnected-(P2-Pad21)") (class "Default")
      (node (ref "P2") (pin "21") (pinfunction "21_21") (pintype "passive+no_connect"))
    )
    (net (code "88") (name "unconnected-(P2-Pad23)") (class "Default")
      (node (ref "P2") (pin "23") (pinfunction "23_23") (pintype "passive+no_connect"))
    )
    (net (code "89") (name "unconnected-(P2-Pad25)") (class "Default")
      (node (ref "P2") (pin "25") (pinfunction "25_25") (pintype "passive+no_connect"))
    )
    (net (code "90") (name "unconnected-(P3-Pad20)") (class "Default")
      (node (ref "P3") (pin "20") (pinfunction "20_20") (pintype "passive+no_connect"))
    )
    (net (code "91") (name "unconnected-(P3-Pad22)") (class "Default")
      (node (ref "P3") (pin "22") (pinfunction "22_22") (pintype "passive+no_connect"))
    )
    (net (code "92") (name "unconnected-(U1-VREF-Pad5)") (class "Default")
      (node (ref "U1") (pin "5") (pinfunction "VREF_5") (pintype "power_in+no_connect"))
    )
    (net (code "93") (name "unconnected-(U2-AN14{slash}PMA1{slash}RPI46{slash}RB14-Pad43)") (class "Default")
      (node (ref "U2") (pin "43") (pinfunction "AN14/PMA1/RPI46/RB14_43") (pintype "bidirectional"))
    )
    (net (code "94") (name "unconnected-(U2-AN15{slash}PMA0{slash}RPI47{slash}RB15-Pad44)") (class "Default")
      (node (ref "U2") (pin "44") (pinfunction "AN15/PMA0/RPI47/RB15_44") (pintype "bidirectional"))
    )
    (net (code "95") (name "unconnected-(U2-AN16{slash}RPI49{slash}RC1-Pad6)") (class "Default")
      (node (ref "U2") (pin "6") (pinfunction "AN16/RPI49/RC1_6") (pintype "bidirectional"))
    )
    (net (code "96") (name "unconnected-(U2-AN17{slash}RPI50{slash}RC2-Pad7)") (class "Default")
      (node (ref "U2") (pin "7") (pinfunction "AN17/RPI50/RC2_7") (pintype "bidirectional"))
    )
    (net (code "97") (name "unconnected-(U2-AN18{slash}RPI51{slash}RC3-Pad8)") (class "Default")
      (node (ref "U2") (pin "8") (pinfunction "AN18/RPI51/RC3_8") (pintype "bidirectional"))
    )
    (net (code "98") (name "unconnected-(U2-AN19{slash}RPI52{slash}RC4-Pad9)") (class "Default")
      (node (ref "U2") (pin "9") (pinfunction "AN19/RPI52/RC4_9") (pintype "bidirectional"))
    )
    (net (code "99") (name "unconnected-(U2-AN22{slash}RPI22{slash}RA6-Pad91)") (class "Default")
      (node (ref "U2") (pin "91") (pinfunction "AN22/RPI22/RA6_91") (pintype "bidirectional"))
    )
    (net (code "100") (name "unconnected-(U2-AN23{slash}RPI23{slash}RA7-Pad92)") (class "Default")
      (node (ref "U2") (pin "92") (pinfunction "AN23/RPI23/RA7_92") (pintype "bidirectional"))
    )
    (net (code "101") (name "unconnected-(U2-RP79{slash}RD15-Pad48)") (class "Default")
      (node (ref "U2") (pin "48") (pinfunction "RP79/RD15_48") (pintype "bidirectional"))
    )
    (net (code "102") (name "unconnected-(U2-RP108{slash}RF12-Pad40)") (class "Default")
      (node (ref "U2") (pin "40") (pinfunction "RP108/RF12_40") (pintype "bidirectional"))
    )
    (net (code "103") (name "unconnected-(U2-RP109{slash}RF13-Pad39)") (class "Default")
      (node (ref "U2") (pin "39") (pinfunction "RP109/RF13_39") (pintype "bidirectional"))
    )
    (net (code "104") (name "unconnected-(U2-RPI30{slash}RA14-Pad66)") (class "Default")
      (node (ref "U2") (pin "66") (pinfunction "RPI30/RA14_66") (pintype "bidirectional"))
    )
    (net (code "105") (name "unconnected-(U2-RPI31{slash}RA15-Pad67)") (class "Default")
      (node (ref "U2") (pin "67") (pinfunction "RPI31/RA15_67") (pintype "bidirectional"))
    )
    (net (code "106") (name "unconnected-(U2-RPI76{slash}RD12-Pad79)") (class "Default")
      (node (ref "U2") (pin "79") (pinfunction "RPI76/RD12_79") (pintype "bidirectional"))
    )
    (net (code "107") (name "unconnected-(U2-RPI77{slash}RD13-Pad80)") (class "Default")
      (node (ref "U2") (pin "80") (pinfunction "RPI77/RD13_80") (pintype "bidirectional"))
    )
    (net (code "108") (name "unconnected-(U2-RPI78{slash}RD14-Pad47)") (class "Default")
      (node (ref "U2") (pin "47") (pinfunction "RPI78/RD14_47") (pintype "bidirectional"))
    )
    (net (code "109") (name "unconnected-(U2-TCK{slash}RPI17{slash}RA1-Pad38)") (class "Default")
      (node (ref "U2") (pin "38") (pinfunction "TCK/RPI17/RA1_38") (pintype "bidirectional"))
    )
    (net (code "110") (name "unconnected-(U2-TDI{slash}RPI20{slash}RA4-Pad60)") (class "Default")
      (node (ref "U2") (pin "60") (pinfunction "TDI/RPI20/RA4_60") (pintype "bidirectional"))
    )
    (net (code "111") (name "unconnected-(U2-TDO{slash}RPI21{slash}RA5-Pad61)") (class "Default")
      (node (ref "U2") (pin "61") (pinfunction "TDO/RPI21/RA5_61") (pintype "bidirectional"))
    )
    (net (code "112") (name "unconnected-(U2-TMS{slash}RPI16{slash}RA0-Pad17)") (class "Default")
      (node (ref "U2") (pin "17") (pinfunction "TMS/RPI16/RA0_17") (pintype "bidirectional"))
    )
    (net (code "113") (name "unconnected-(U2-VREF+{slash}RA10-Pad29)") (class "Default")
      (node (ref "U2") (pin "29") (pinfunction "VREF+/RA10_29") (pintype "passive"))
    )
    (net (code "114") (name "unconnected-(U2-VREF-{slash}RA9-Pad28)") (class "Default")
      (node (ref "U2") (pin "28") (pinfunction "VREF-/RA9_28") (pintype "passive"))
    )
    (net (code "115") (name "unconnected-(U3-NC-Pad3)") (class "Default")
      (node (ref "U3") (pin "3") (pinfunction "NC_3") (pintype "passive+no_connect"))
    )
    (net (code "116") (name "unconnected-(U3-NC-Pad6)") (class "Default")
      (node (ref "U3") (pin "6") (pinfunction "NC_6") (pintype "passive+no_connect"))
    )
  )
)
